# MAX2871.net
KiCad netlist of a schematic drawn in EAGLE
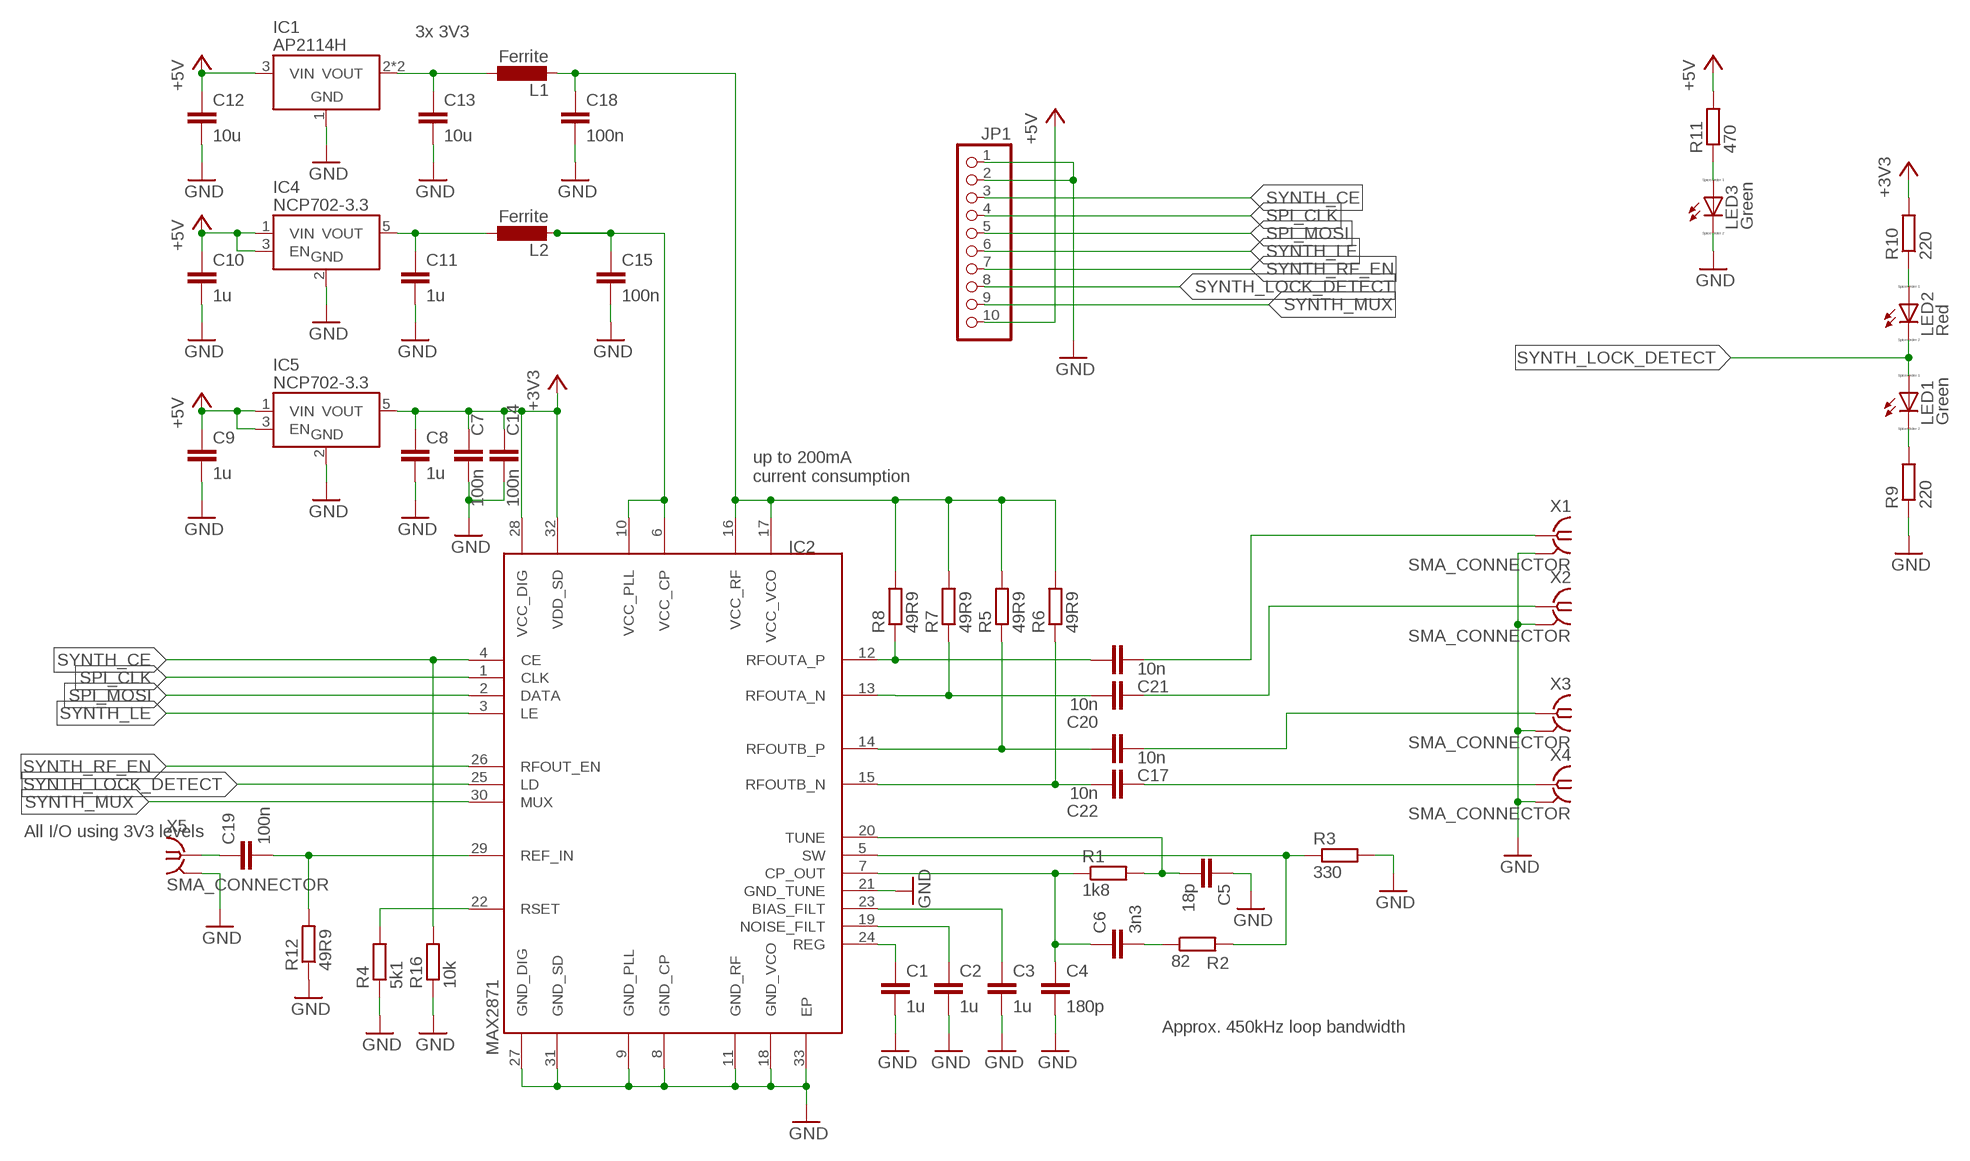
[diagram p0: schematic, sheet 1]

(export (version "E")
  (design (tool "Eeschema 10.0.6"))
  (components
    (comp (ref "C1")
      (value "1u")
      (footprint "eagle-import:C0603")
      (libsource (lib "eagle-import") (part "C-EUC0603"))
    )
    (comp (ref "C2")
      (value "1u")
      (footprint "eagle-import:C0603")
      (libsource (lib "eagle-import") (part "C-EUC0603"))
    )
    (comp (ref "C3")
      (value "1u")
      (footprint "eagle-import:C0603")
      (libsource (lib "eagle-import") (part "C-EUC0603"))
    )
    (comp (ref "C4")
      (value "180p")
      (footprint "eagle-import:C0603")
      (libsource (lib "eagle-import") (part "C-EUC0603"))
    )
    (comp (ref "C5")
      (value "18p")
      (footprint "eagle-import:C0603")
      (libsource (lib "eagle-import") (part "C-EUC0603"))
    )
    (comp (ref "C6")
      (value "3n3")
      (footprint "eagle-import:C0603")
      (libsource (lib "eagle-import") (part "C-EUC0603"))
    )
    (comp (ref "C7")
      (value "100n")
      (footprint "eagle-import:C0603")
      (libsource (lib "eagle-import") (part "C-EUC0603"))
    )
    (comp (ref "C8")
      (value "1u")
      (footprint "eagle-import:C0603")
      (libsource (lib "eagle-import") (part "C-EUC0603"))
    )
    (comp (ref "C9")
      (value "1u")
      (footprint "eagle-import:C0603")
      (libsource (lib "eagle-import") (part "C-EUC0603"))
    )
    (comp (ref "C10")
      (value "1u")
      (footprint "eagle-import:C0603")
      (libsource (lib "eagle-import") (part "C-EUC0603"))
    )
    (comp (ref "C11")
      (value "1u")
      (footprint "eagle-import:C0603")
      (libsource (lib "eagle-import") (part "C-EUC0603"))
    )
    (comp (ref "C12")
      (value "10u")
      (footprint "eagle-import:C1206")
      (libsource (lib "eagle-import") (part "C-EUC1206"))
    )
    (comp (ref "C13")
      (value "10u")
      (footprint "eagle-import:C1206")
      (libsource (lib "eagle-import") (part "C-EUC1206"))
    )
    (comp (ref "C14")
      (value "100n")
      (footprint "eagle-import:C0603")
      (libsource (lib "eagle-import") (part "C-EUC0603"))
    )
    (comp (ref "C15")
      (value "100n")
      (footprint "eagle-import:C0603")
      (libsource (lib "eagle-import") (part "C-EUC0603"))
    )
    (comp (ref "C17")
      (value "10n")
      (footprint "eagle-import:C0603")
      (libsource (lib "eagle-import") (part "C-EUC0603"))
    )
    (comp (ref "C18")
      (value "100n")
      (footprint "eagle-import:C0603")
      (libsource (lib "eagle-import") (part "C-EUC0603"))
    )
    (comp (ref "C19")
      (value "100n")
      (footprint "eagle-import:C0603")
      (libsource (lib "eagle-import") (part "C-EUC0603"))
    )
    (comp (ref "C20")
      (value "10n")
      (footprint "eagle-import:C0603")
      (libsource (lib "eagle-import") (part "C-EUC0603"))
    )
    (comp (ref "C21")
      (value "10n")
      (footprint "eagle-import:C0603")
      (libsource (lib "eagle-import") (part "C-EUC0603"))
    )
    (comp (ref "C22")
      (value "10n")
      (footprint "eagle-import:C0603")
      (libsource (lib "eagle-import") (part "C-EUC0603"))
    )
    (comp (ref "IC1")
      (value "AP2114H")
      (footprint "eagle-import:SOT230P700X180-4")
      (libsource (lib "eagle-import") (part "AP2114H"))
    )
    (comp (ref "IC2")
      (value "MAX2871")
      (footprint "eagle-import:QFN50P500X500X80-33T310")
      (libsource (lib "eagle-import") (part "MAX2871"))
    )
    (comp (ref "IC4")
      (value "NCP702-3.3")
      (footprint "eagle-import:SOT95P240X110-5")
      (libsource (lib "eagle-import") (part "NCP702"))
    )
    (comp (ref "IC5")
      (value "NCP702-3.3")
      (footprint "eagle-import:SOT95P240X110-5")
      (libsource (lib "eagle-import") (part "NCP702"))
    )
    (comp (ref "JP1")
      (value "PINHD-1X10/90")
      (footprint "eagle-import:1X10_90")
      (libsource (lib "eagle-import") (part "PINHD-1X10/90"))
    )
    (comp (ref "L1")
      (value "Ferrite")
      (footprint "eagle-import:R0603")
      (libsource (lib "eagle-import") (part "INDUCTOR0603"))
    )
    (comp (ref "L2")
      (value "Ferrite")
      (footprint "eagle-import:R0603")
      (libsource (lib "eagle-import") (part "INDUCTOR0603"))
    )
    (comp (ref "LED1")
      (value "Green")
      (footprint "eagle-import:LED_SML0603")
      (libsource (lib "eagle-import") (part "LED_ESML0603"))
    )
    (comp (ref "LED2")
      (value "Red")
      (footprint "eagle-import:LED_SML0603")
      (libsource (lib "eagle-import") (part "LED_ESML0603"))
    )
    (comp (ref "LED3")
      (value "Green")
      (footprint "eagle-import:LED_SML0603")
      (libsource (lib "eagle-import") (part "LED_ESML0603"))
    )
    (comp (ref "R1")
      (value "1k8")
      (footprint "eagle-import:R0603")
      (libsource (lib "eagle-import") (part "R-EU_R0603"))
    )
    (comp (ref "R2")
      (value "82")
      (footprint "eagle-import:R0603")
      (libsource (lib "eagle-import") (part "R-EU_R0603"))
    )
    (comp (ref "R3")
      (value "330")
      (footprint "eagle-import:R0603")
      (libsource (lib "eagle-import") (part "R-EU_R0603"))
    )
    (comp (ref "R4")
      (value "5k1")
      (footprint "eagle-import:R0603")
      (libsource (lib "eagle-import") (part "R-EU_R0603"))
    )
    (comp (ref "R5")
      (value "49R9")
      (footprint "eagle-import:R0603")
      (libsource (lib "eagle-import") (part "R-EU_R0603"))
    )
    (comp (ref "R6")
      (value "49R9")
      (footprint "eagle-import:R0603")
      (libsource (lib "eagle-import") (part "R-EU_R0603"))
    )
    (comp (ref "R7")
      (value "49R9")
      (footprint "eagle-import:R0603")
      (libsource (lib "eagle-import") (part "R-EU_R0603"))
    )
    (comp (ref "R8")
      (value "49R9")
      (footprint "eagle-import:R0603")
      (libsource (lib "eagle-import") (part "R-EU_R0603"))
    )
    (comp (ref "R9")
      (value "220")
      (footprint "eagle-import:R0603")
      (libsource (lib "eagle-import") (part "R-EU_R0603"))
    )
    (comp (ref "R10")
      (value "220")
      (footprint "eagle-import:R0603")
      (libsource (lib "eagle-import") (part "R-EU_R0603"))
    )
    (comp (ref "R11")
      (value "470")
      (footprint "eagle-import:R0603")
      (libsource (lib "eagle-import") (part "R-EU_R0603"))
    )
    (comp (ref "R12")
      (value "49R9")
      (footprint "eagle-import:R0603")
      (libsource (lib "eagle-import") (part "R-EU_R0603"))
    )
    (comp (ref "R16")
      (value "10k")
      (footprint "eagle-import:R0603")
      (libsource (lib "eagle-import") (part "R-EU_R0603"))
    )
    (comp (ref "X1")
      (value "SMA_CONNECTOR")
      (footprint "eagle-import:J502-ND-142-0711-821_826")
      (libsource (lib "eagle-import") (part "SMA_CONNECTOR"))
    )
    (comp (ref "X2")
      (value "SMA_CONNECTOR")
      (footprint "eagle-import:J502-ND-142-0711-821_826")
      (libsource (lib "eagle-import") (part "SMA_CONNECTOR"))
    )
    (comp (ref "X3")
      (value "SMA_CONNECTOR")
      (footprint "eagle-import:J502-ND-142-0711-821_826")
      (libsource (lib "eagle-import") (part "SMA_CONNECTOR"))
    )
    (comp (ref "X4")
      (value "SMA_CONNECTOR")
      (footprint "eagle-import:J502-ND-142-0711-821_826")
      (libsource (lib "eagle-import") (part "SMA_CONNECTOR"))
    )
    (comp (ref "X5")
      (value "SMA_CONNECTOR")
      (footprint "eagle-import:J502-ND-142-0711-821_826")
      (libsource (lib "eagle-import") (part "SMA_CONNECTOR"))
    )
  )
  (nets
    (net (code "1") (name "+3V3") (class "Default")
      (node (ref "C14") (pin "1") (pinfunction "1_1") (pintype "passive"))
      (node (ref "C7") (pin "1") (pinfunction "1_1") (pintype "passive"))
      (node (ref "C8") (pin "1") (pinfunction "1_1") (pintype "passive"))
      (node (ref "IC2") (pin "28") (pinfunction "VCC_DIG_28") (pintype "bidirectional"))
      (node (ref "IC2") (pin "32") (pinfunction "VDD_SD_32") (pintype "bidirectional"))
      (node (ref "IC5") (pin "5") (pinfunction "VOUT_5") (pintype "power_in"))
      (node (ref "R10") (pin "2") (pinfunction "2_2") (pintype "passive"))
    )
    (net (code "2") (name "+5V") (class "Default")
      (node (ref "C10") (pin "1") (pinfunction "1_1") (pintype "passive"))
      (node (ref "C12") (pin "1") (pinfunction "1_1") (pintype "passive"))
      (node (ref "C9") (pin "1") (pinfunction "1_1") (pintype "passive"))
      (node (ref "IC1") (pin "3") (pinfunction "VIN_3") (pintype "power_in"))
      (node (ref "IC4") (pin "1") (pinfunction "VIN_1") (pintype "power_in"))
      (node (ref "IC4") (pin "3") (pinfunction "EN_3") (pintype "input"))
      (node (ref "IC5") (pin "1") (pinfunction "VIN_1") (pintype "power_in"))
      (node (ref "IC5") (pin "3") (pinfunction "EN_3") (pintype "input"))
      (node (ref "JP1") (pin "10") (pinfunction "10_10") (pintype "passive"))
      (node (ref "R11") (pin "2") (pinfunction "2_2") (pintype "passive"))
    )
    (net (code "3") (name "GND") (class "Default")
      (node (ref "C1") (pin "2") (pinfunction "2_2") (pintype "passive"))
      (node (ref "C10") (pin "2") (pinfunction "2_2") (pintype "passive"))
      (node (ref "C11") (pin "2") (pinfunction "2_2") (pintype "passive"))
      (node (ref "C12") (pin "2") (pinfunction "2_2") (pintype "passive"))
      (node (ref "C13") (pin "2") (pinfunction "2_2") (pintype "passive"))
      (node (ref "C14") (pin "2") (pinfunction "2_2") (pintype "passive"))
      (node (ref "C15") (pin "2") (pinfunction "2_2") (pintype "passive"))
      (node (ref "C18") (pin "2") (pinfunction "2_2") (pintype "passive"))
      (node (ref "C2") (pin "2") (pinfunction "2_2") (pintype "passive"))
      (node (ref "C3") (pin "2") (pinfunction "2_2") (pintype "passive"))
      (node (ref "C4") (pin "2") (pinfunction "2_2") (pintype "passive"))
      (node (ref "C5") (pin "1") (pinfunction "1_1") (pintype "passive"))
      (node (ref "C7") (pin "2") (pinfunction "2_2") (pintype "passive"))
      (node (ref "C8") (pin "2") (pinfunction "2_2") (pintype "passive"))
      (node (ref "C9") (pin "2") (pinfunction "2_2") (pintype "passive"))
      (node (ref "IC1") (pin "1") (pinfunction "GND_1") (pintype "power_in"))
      (node (ref "IC2") (pin "11") (pinfunction "GND_RF_11") (pintype "bidirectional"))
      (node (ref "IC2") (pin "18") (pinfunction "GND_VCO_18") (pintype "bidirectional"))
      (node (ref "IC2") (pin "21") (pinfunction "GND_TUNE_21") (pintype "bidirectional"))
      (node (ref "IC2") (pin "27") (pinfunction "GND_DIG_27") (pintype "bidirectional"))
      (node (ref "IC2") (pin "31") (pinfunction "GND_SD_31") (pintype "bidirectional"))
      (node (ref "IC2") (pin "33") (pinfunction "EP_33") (pintype "bidirectional"))
      (node (ref "IC2") (pin "8") (pinfunction "GND_CP_8") (pintype "bidirectional"))
      (node (ref "IC2") (pin "9") (pinfunction "GND_PLL_9") (pintype "bidirectional"))
      (node (ref "IC4") (pin "2") (pinfunction "GND_2") (pintype "power_in"))
      (node (ref "IC5") (pin "2") (pinfunction "GND_2") (pintype "power_in"))
      (node (ref "JP1") (pin "1") (pinfunction "1_1") (pintype "passive"))
      (node (ref "JP1") (pin "2") (pinfunction "2_2") (pintype "passive"))
      (node (ref "LED3") (pin "C") (pinfunction "C_C") (pintype "passive"))
      (node (ref "R12") (pin "1") (pinfunction "1_1") (pintype "passive"))
      (node (ref "R16") (pin "1") (pinfunction "1_1") (pintype "passive"))
      (node (ref "R3") (pin "2") (pinfunction "2_2") (pintype "passive"))
      (node (ref "R4") (pin "1") (pinfunction "1_1") (pintype "passive"))
      (node (ref "R9") (pin "1") (pinfunction "1_1") (pintype "passive"))
      (node (ref "X1") (pin "G@1") (pinfunction "2_G@1") (pintype "passive"))
      (node (ref "X1") (pin "G@2") (pinfunction "2_G@2") (pintype "passive"))
      (node (ref "X1") (pin "G@3") (pinfunction "2_G@3") (pintype "passive"))
      (node (ref "X1") (pin "G@4") (pinfunction "2_G@4") (pintype "passive"))
      (node (ref "X2") (pin "G@1") (pinfunction "2_G@1") (pintype "passive"))
      (node (ref "X2") (pin "G@2") (pinfunction "2_G@2") (pintype "passive"))
      (node (ref "X2") (pin "G@3") (pinfunction "2_G@3") (pintype "passive"))
      (node (ref "X2") (pin "G@4") (pinfunction "2_G@4") (pintype "passive"))
      (node (ref "X3") (pin "G@1") (pinfunction "2_G@1") (pintype "passive"))
      (node (ref "X3") (pin "G@2") (pinfunction "2_G@2") (pintype "passive"))
      (node (ref "X3") (pin "G@3") (pinfunction "2_G@3") (pintype "passive"))
      (node (ref "X3") (pin "G@4") (pinfunction "2_G@4") (pintype "passive"))
      (node (ref "X4") (pin "G@1") (pinfunction "2_G@1") (pintype "passive"))
      (node (ref "X4") (pin "G@2") (pinfunction "2_G@2") (pintype "passive"))
      (node (ref "X4") (pin "G@3") (pinfunction "2_G@3") (pintype "passive"))
      (node (ref "X4") (pin "G@4") (pinfunction "2_G@4") (pintype "passive"))
      (node (ref "X5") (pin "G@1") (pinfunction "2_G@1") (pintype "passive"))
      (node (ref "X5") (pin "G@2") (pinfunction "2_G@2") (pintype "passive"))
      (node (ref "X5") (pin "G@3") (pinfunction "2_G@3") (pintype "passive"))
      (node (ref "X5") (pin "G@4") (pinfunction "2_G@4") (pintype "passive"))
    )
    (net (code "4") (name "Net-(C6-Pad2)") (class "Default")
      (node (ref "C6") (pin "2") (pinfunction "2_2") (pintype "passive"))
      (node (ref "R2") (pin "1") (pinfunction "1_1") (pintype "passive"))
    )
    (net (code "5") (name "Net-(C13-Pad1)") (class "Default")
      (node (ref "C13") (pin "1") (pinfunction "1_1") (pintype "passive"))
      (node (ref "IC1") (pin "2") (pinfunction "VOUT_2") (pintype "power_in"))
      (node (ref "IC1") (pin "4") (pinfunction "VOUT_4") (pintype "power_in"))
      (node (ref "L1") (pin "1") (pinfunction "1_1") (pintype "passive"))
    )
    (net (code "6") (name "Net-(C17-Pad2)") (class "Default")
      (node (ref "C17") (pin "2") (pinfunction "2_2") (pintype "passive"))
      (node (ref "X3") (pin "1") (pinfunction "1_1") (pintype "passive"))
    )
    (net (code "7") (name "Net-(C19-Pad1)") (class "Default")
      (node (ref "C19") (pin "1") (pinfunction "1_1") (pintype "passive"))
      (node (ref "X5") (pin "1") (pinfunction "1_1") (pintype "passive"))
    )
    (net (code "8") (name "Net-(C20-Pad1)") (class "Default")
      (node (ref "C20") (pin "1") (pinfunction "1_1") (pintype "passive"))
      (node (ref "X2") (pin "1") (pinfunction "1_1") (pintype "passive"))
    )
    (net (code "9") (name "Net-(C21-Pad2)") (class "Default")
      (node (ref "C21") (pin "2") (pinfunction "2_2") (pintype "passive"))
      (node (ref "X1") (pin "1") (pinfunction "1_1") (pintype "passive"))
    )
    (net (code "10") (name "Net-(C22-Pad1)") (class "Default")
      (node (ref "C22") (pin "1") (pinfunction "1_1") (pintype "passive"))
      (node (ref "X4") (pin "1") (pinfunction "1_1") (pintype "passive"))
    )
    (net (code "11") (name "Net-(IC2-BIAS_FILT)") (class "Default")
      (node (ref "C3") (pin "1") (pinfunction "1_1") (pintype "passive"))
      (node (ref "IC2") (pin "23") (pinfunction "BIAS_FILT_23") (pintype "bidirectional"))
    )
    (net (code "12") (name "Net-(IC2-CP_OUT)") (class "Default")
      (node (ref "C4") (pin "1") (pinfunction "1_1") (pintype "passive"))
      (node (ref "C6") (pin "1") (pinfunction "1_1") (pintype "passive"))
      (node (ref "IC2") (pin "7") (pinfunction "CP_OUT_7") (pintype "bidirectional"))
      (node (ref "R1") (pin "1") (pinfunction "1_1") (pintype "passive"))
    )
    (net (code "13") (name "Net-(IC2-NOISE_FILT)") (class "Default")
      (node (ref "C2") (pin "1") (pinfunction "1_1") (pintype "passive"))
      (node (ref "IC2") (pin "19") (pinfunction "NOISE_FILT_19") (pintype "bidirectional"))
    )
    (net (code "14") (name "Net-(IC2-REF_IN)") (class "Default")
      (node (ref "C19") (pin "2") (pinfunction "2_2") (pintype "passive"))
      (node (ref "IC2") (pin "29") (pinfunction "REF_IN_29") (pintype "input"))
      (node (ref "R12") (pin "2") (pinfunction "2_2") (pintype "passive"))
    )
    (net (code "15") (name "Net-(IC2-REG)") (class "Default")
      (node (ref "C1") (pin "1") (pinfunction "1_1") (pintype "passive"))
      (node (ref "IC2") (pin "24") (pinfunction "REG_24") (pintype "bidirectional"))
    )
    (net (code "16") (name "Net-(IC2-RFOUTA_N)") (class "Default")
      (node (ref "C20") (pin "2") (pinfunction "2_2") (pintype "passive"))
      (node (ref "IC2") (pin "13") (pinfunction "RFOUTA_N_13") (pintype "bidirectional"))
      (node (ref "R7") (pin "1") (pinfunction "1_1") (pintype "passive"))
    )
    (net (code "17") (name "Net-(IC2-RFOUTA_P)") (class "Default")
      (node (ref "C21") (pin "1") (pinfunction "1_1") (pintype "passive"))
      (node (ref "IC2") (pin "12") (pinfunction "RFOUTA_P_12") (pintype "bidirectional"))
      (node (ref "R8") (pin "1") (pinfunction "1_1") (pintype "passive"))
    )
    (net (code "18") (name "Net-(IC2-RFOUTB_N)") (class "Default")
      (node (ref "C22") (pin "2") (pinfunction "2_2") (pintype "passive"))
      (node (ref "IC2") (pin "15") (pinfunction "RFOUTB_N_15") (pintype "bidirectional"))
      (node (ref "R6") (pin "1") (pinfunction "1_1") (pintype "passive"))
    )
    (net (code "19") (name "Net-(IC2-RFOUTB_P)") (class "Default")
      (node (ref "C17") (pin "1") (pinfunction "1_1") (pintype "passive"))
      (node (ref "IC2") (pin "14") (pinfunction "RFOUTB_P_14") (pintype "bidirectional"))
      (node (ref "R5") (pin "1") (pinfunction "1_1") (pintype "passive"))
    )
    (net (code "20") (name "Net-(IC2-RSET)") (class "Default")
      (node (ref "IC2") (pin "22") (pinfunction "RSET_22") (pintype "bidirectional"))
      (node (ref "R4") (pin "2") (pinfunction "2_2") (pintype "passive"))
    )
    (net (code "21") (name "Net-(IC2-SW)") (class "Default")
      (node (ref "IC2") (pin "5") (pinfunction "SW_5") (pintype "bidirectional"))
      (node (ref "R2") (pin "2") (pinfunction "2_2") (pintype "passive"))
      (node (ref "R3") (pin "1") (pinfunction "1_1") (pintype "passive"))
    )
    (net (code "22") (name "Net-(IC2-TUNE)") (class "Default")
      (node (ref "C5") (pin "2") (pinfunction "2_2") (pintype "passive"))
      (node (ref "IC2") (pin "20") (pinfunction "TUNE_20") (pintype "bidirectional"))
      (node (ref "R1") (pin "2") (pinfunction "2_2") (pintype "passive"))
    )
    (net (code "23") (name "Net-(IC2-VCC_CP)") (class "Default")
      (node (ref "C15") (pin "1") (pinfunction "1_1") (pintype "passive"))
      (node (ref "IC2") (pin "10") (pinfunction "VCC_PLL_10") (pintype "bidirectional"))
      (node (ref "IC2") (pin "6") (pinfunction "VCC_CP_6") (pintype "bidirectional"))
      (node (ref "L2") (pin "2") (pinfunction "2_2") (pintype "passive"))
    )
    (net (code "24") (name "Net-(IC2-VCC_RF)") (class "Default")
      (node (ref "C18") (pin "1") (pinfunction "1_1") (pintype "passive"))
      (node (ref "IC2") (pin "16") (pinfunction "VCC_RF_16") (pintype "bidirectional"))
      (node (ref "IC2") (pin "17") (pinfunction "VCC_VCO_17") (pintype "bidirectional"))
      (node (ref "L1") (pin "2") (pinfunction "2_2") (pintype "passive"))
      (node (ref "R5") (pin "2") (pinfunction "2_2") (pintype "passive"))
      (node (ref "R6") (pin "2") (pinfunction "2_2") (pintype "passive"))
      (node (ref "R7") (pin "2") (pinfunction "2_2") (pintype "passive"))
      (node (ref "R8") (pin "2") (pinfunction "2_2") (pintype "passive"))
    )
    (net (code "25") (name "Net-(IC4-VOUT)") (class "Default")
      (node (ref "C11") (pin "1") (pinfunction "1_1") (pintype "passive"))
      (node (ref "IC4") (pin "5") (pinfunction "VOUT_5") (pintype "power_in"))
      (node (ref "L2") (pin "1") (pinfunction "1_1") (pintype "passive"))
    )
    (net (code "26") (name "Net-(LED1-PadC)") (class "Default")
      (node (ref "LED1") (pin "C") (pinfunction "C_C") (pintype "passive"))
      (node (ref "R9") (pin "2") (pinfunction "2_2") (pintype "passive"))
    )
    (net (code "27") (name "Net-(LED2-PadA)") (class "Default")
      (node (ref "LED2") (pin "A") (pinfunction "A_A") (pintype "passive"))
      (node (ref "R10") (pin "1") (pinfunction "1_1") (pintype "passive"))
    )
    (net (code "28") (name "Net-(LED3-PadA)") (class "Default")
      (node (ref "LED3") (pin "A") (pinfunction "A_A") (pintype "passive"))
      (node (ref "R11") (pin "1") (pinfunction "1_1") (pintype "passive"))
    )
    (net (code "29") (name "SPI_CLK") (class "Default")
      (node (ref "IC2") (pin "1") (pinfunction "CLK_1") (pintype "input"))
      (node (ref "JP1") (pin "4") (pinfunction "4_4") (pintype "passive"))
    )
    (net (code "30") (name "SPI_MOSI") (class "Default")
      (node (ref "IC2") (pin "2") (pinfunction "DATA_2") (pintype "input"))
      (node (ref "JP1") (pin "5") (pinfunction "5_5") (pintype "passive"))
    )
    (net (code "31") (name "SYNTH_CE") (class "Default")
      (node (ref "IC2") (pin "4") (pinfunction "CE_4") (pintype "bidirectional"))
      (node (ref "JP1") (pin "3") (pinfunction "3_3") (pintype "passive"))
      (node (ref "R16") (pin "2") (pinfunction "2_2") (pintype "passive"))
    )
    (net (code "32") (name "SYNTH_LE") (class "Default")
      (node (ref "IC2") (pin "3") (pinfunction "LE_3") (pintype "input"))
      (node (ref "JP1") (pin "6") (pinfunction "6_6") (pintype "passive"))
    )
    (net (code "33") (name "SYNTH_LOCK_DETECT") (class "Default")
      (node (ref "IC2") (pin "25") (pinfunction "LD_25") (pintype "output"))
      (node (ref "JP1") (pin "8") (pinfunction "8_8") (pintype "passive"))
      (node (ref "LED1") (pin "A") (pinfunction "A_A") (pintype "passive"))
      (node (ref "LED2") (pin "C") (pinfunction "C_C") (pintype "passive"))
    )
    (net (code "34") (name "SYNTH_MUX") (class "Default")
      (node (ref "IC2") (pin "30") (pinfunction "MUX_30") (pintype "bidirectional"))
      (node (ref "JP1") (pin "9") (pinfunction "9_9") (pintype "passive"))
    )
    (net (code "35") (name "SYNTH_RF_EN") (class "Default")
      (node (ref "IC2") (pin "26") (pinfunction "RFOUT_EN_26") (pintype "input"))
      (node (ref "JP1") (pin "7") (pinfunction "7_7") (pintype "passive"))
    )
  )
)
